# distortion-noise-and-ring-modulator-v1_1.net
KiCad netlist of a schematic drawn in EAGLE
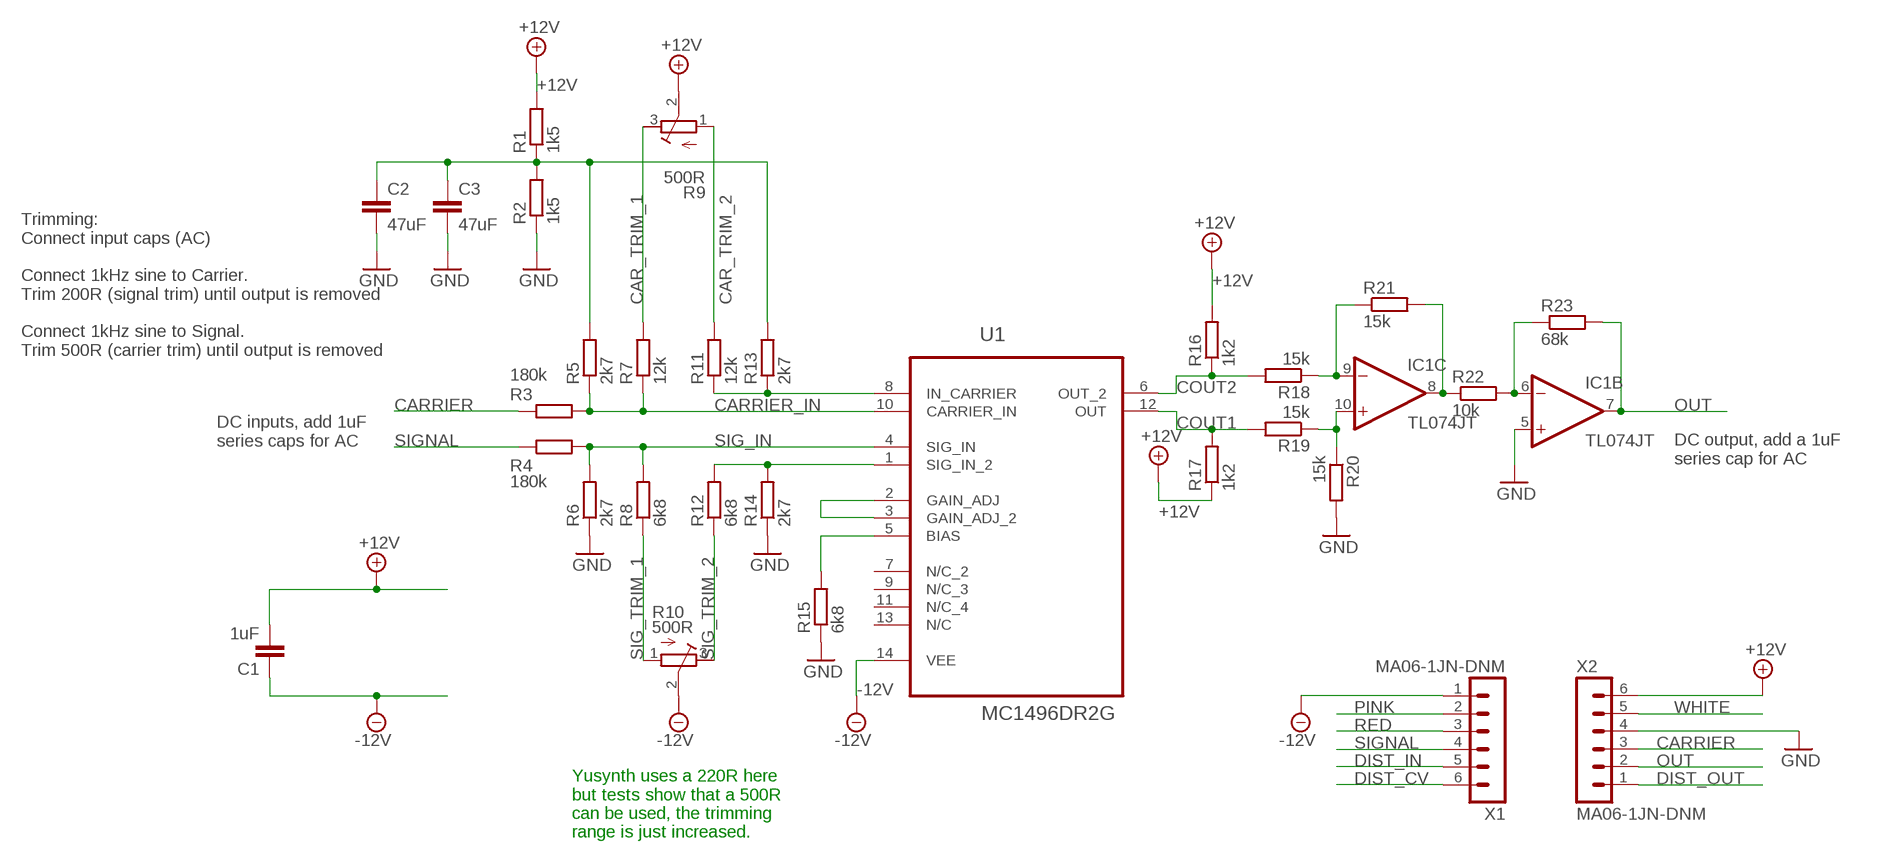
[diagram p0: schematic, sheet 1]
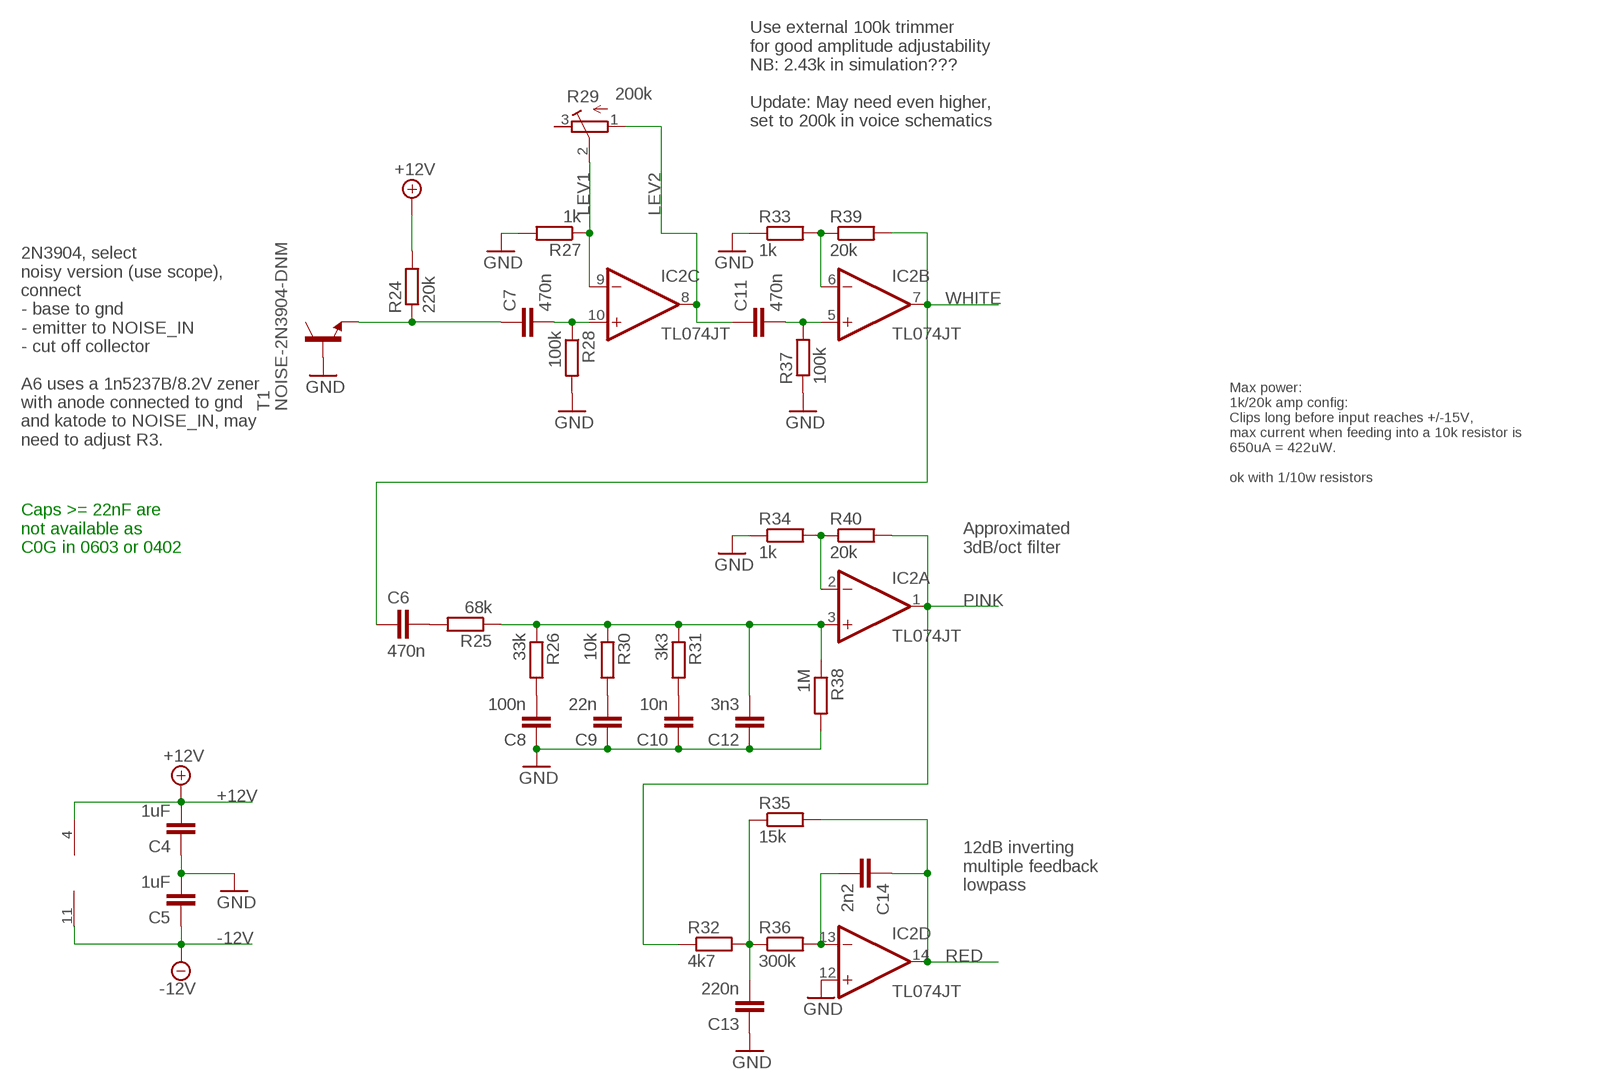
[diagram p1: schematic, sheet 2]
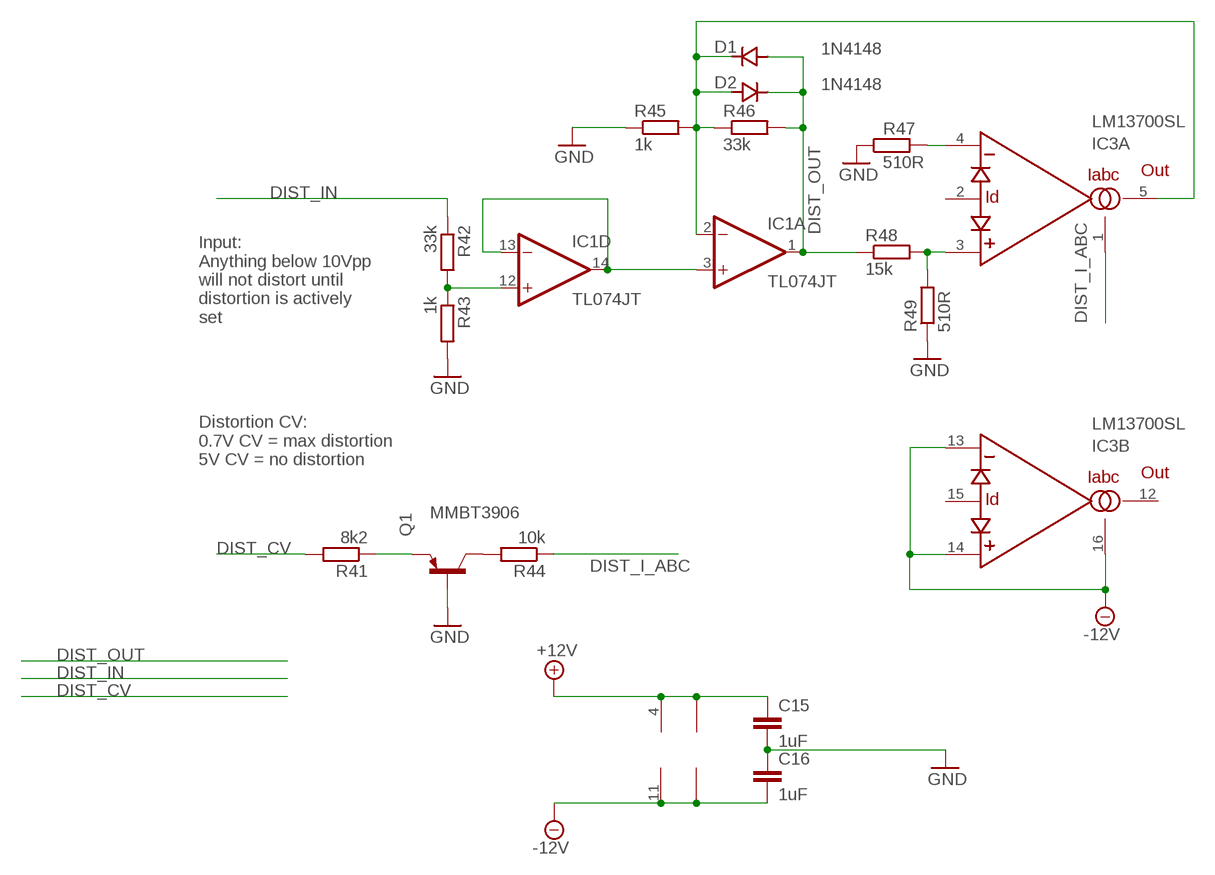
[diagram p2: schematic, sheet 3]

(export (version "E")
  (design (tool "Eeschema 10.0.6"))
  (components
    (comp (ref "C4")
      (value "1uF")
      (footprint "eagle-import:C0402-J")
      (libsource (lib "eagle-import") (part "C-EU-J0402"))
    )
    (comp (ref "C5")
      (value "1uF")
      (footprint "eagle-import:C0402-J")
      (libsource (lib "eagle-import") (part "C-EU-J0402"))
    )
    (comp (ref "C6")
      (value "470n")
      (footprint "eagle-import:C0603-J")
      (libsource (lib "eagle-import") (part "C-EU-J0603"))
    )
    (comp (ref "C7")
      (value "470n")
      (footprint "eagle-import:C0603-J")
      (libsource (lib "eagle-import") (part "C-EU-J0603"))
    )
    (comp (ref "C8")
      (value "100n")
      (footprint "eagle-import:C0402-J")
      (libsource (lib "eagle-import") (part "C-EU-J0402"))
    )
    (comp (ref "C9")
      (value "22n")
      (footprint "eagle-import:C0402-J")
      (libsource (lib "eagle-import") (part "C-EU-J0402"))
    )
    (comp (ref "C10")
      (value "10n")
      (footprint "eagle-import:C0402-J")
      (libsource (lib "eagle-import") (part "C-EU-J0402"))
    )
    (comp (ref "C11")
      (value "470n")
      (footprint "eagle-import:C0603-J")
      (libsource (lib "eagle-import") (part "C-EU-J0603"))
    )
    (comp (ref "C12")
      (value "3n3")
      (footprint "eagle-import:C0603-J")
      (libsource (lib "eagle-import") (part "C-EU-J0603"))
    )
    (comp (ref "C13")
      (value "220n")
      (footprint "eagle-import:C0402-J")
      (libsource (lib "eagle-import") (part "C-EU-J0402"))
    )
    (comp (ref "C14")
      (value "2n2")
      (footprint "eagle-import:C0603-J")
      (libsource (lib "eagle-import") (part "C-EU-J0603"))
    )
    (comp (ref "IC2")
      (value "TL074JT")
      (footprint "eagle-import:TSSOP14J")
      (libsource (lib "eagle-import") (part "TL074JT"))
    )
    (comp (ref "R24")
      (value "220k")
      (footprint "eagle-import:R0603")
      (libsource (lib "eagle-import") (part "R-EU_R0603"))
    )
    (comp (ref "R25")
      (value "68k")
      (footprint "eagle-import:R0603")
      (libsource (lib "eagle-import") (part "R-EU_R0603"))
    )
    (comp (ref "R26")
      (value "33k")
      (footprint "eagle-import:R0402")
      (libsource (lib "eagle-import") (part "R-EU_R0402"))
    )
    (comp (ref "R27")
      (value "1k")
      (footprint "eagle-import:R0402")
      (libsource (lib "eagle-import") (part "R-EU_R0402"))
    )
    (comp (ref "R28")
      (value "100k")
      (footprint "eagle-import:R0402")
      (libsource (lib "eagle-import") (part "R-EU_R0402"))
    )
    (comp (ref "R29")
      (value "200k")
      (footprint "eagle-import:RTRIM3296W")
      (libsource (lib "eagle-import") (part "R-TRIMM3296W"))
    )
    (comp (ref "R30")
      (value "10k")
      (footprint "eagle-import:R0402")
      (libsource (lib "eagle-import") (part "R-EU_R0402"))
    )
    (comp (ref "R31")
      (value "3k3")
      (footprint "eagle-import:R0402")
      (libsource (lib "eagle-import") (part "R-EU_R0402"))
    )
    (comp (ref "R32")
      (value "4k7")
      (footprint "eagle-import:R0402")
      (libsource (lib "eagle-import") (part "R-EU_R0402"))
    )
    (comp (ref "R33")
      (value "1k")
      (footprint "eagle-import:R0402")
      (libsource (lib "eagle-import") (part "R-EU_R0402"))
    )
    (comp (ref "R34")
      (value "1k")
      (footprint "eagle-import:R0402")
      (libsource (lib "eagle-import") (part "R-EU_R0402"))
    )
    (comp (ref "R35")
      (value "15k")
      (footprint "eagle-import:R0402")
      (libsource (lib "eagle-import") (part "R-EU_R0402"))
    )
    (comp (ref "R36")
      (value "300k")
      (footprint "eagle-import:R0603")
      (libsource (lib "eagle-import") (part "R-EU_R0603"))
    )
    (comp (ref "R37")
      (value "100k")
      (footprint "eagle-import:R0402")
      (libsource (lib "eagle-import") (part "R-EU_R0402"))
    )
    (comp (ref "R38")
      (value "1M")
      (footprint "eagle-import:R0402")
      (libsource (lib "eagle-import") (part "R-EU_R0402"))
    )
    (comp (ref "R39")
      (value "20k")
      (footprint "eagle-import:R0402")
      (libsource (lib "eagle-import") (part "R-EU_R0402"))
    )
    (comp (ref "R40")
      (value "20k")
      (footprint "eagle-import:R0402")
      (libsource (lib "eagle-import") (part "R-EU_R0402"))
    )
    (comp (ref "T1")
      (value "NOISE-2N3904-DNM")
      (footprint "eagle-import:NOISE-2N3904-J")
      (libsource (lib "eagle-import") (part "NOISE-2N3904"))
    )
    (comp (ref "C15")
      (value "1uF")
      (footprint "eagle-import:C0402-J")
      (libsource (lib "eagle-import") (part "C-EU-J0402"))
    )
    (comp (ref "C16")
      (value "1uF")
      (footprint "eagle-import:C0402-J")
      (libsource (lib "eagle-import") (part "C-EU-J0402"))
    )
    (comp (ref "D1")
      (value "1N4148")
      (footprint "eagle-import:SOD323J")
      (libsource (lib "eagle-import") (part "1N4148SOD323"))
    )
    (comp (ref "D2")
      (value "1N4148")
      (footprint "eagle-import:SOD323J")
      (libsource (lib "eagle-import") (part "1N4148SOD323"))
    )
    (comp (ref "IC1")
      (value "TL074JT")
      (footprint "eagle-import:TSSOP14J")
      (libsource (lib "eagle-import") (part "TL074JT"))
    )
    (comp (ref "IC3")
      (value "LM13700SL")
      (footprint "eagle-import:SO16-NARROW-J")
      (libsource (lib "eagle-import") (part "LM13700SL"))
    )
    (comp (ref "Q1")
      (value "MMBT3906")
      (footprint "eagle-import:SOT23-BEC")
      (libsource (lib "eagle-import") (part "MMBT3906SMDLT1"))
    )
    (comp (ref "R41")
      (value "8k2")
      (footprint "eagle-import:R0603")
      (libsource (lib "eagle-import") (part "R-EU_R0603"))
    )
    (comp (ref "R42")
      (value "33k")
      (footprint "eagle-import:R0402")
      (libsource (lib "eagle-import") (part "R-EU_R0402"))
    )
    (comp (ref "R43")
      (value "1k")
      (footprint "eagle-import:R0402")
      (libsource (lib "eagle-import") (part "R-EU_R0402"))
    )
    (comp (ref "R44")
      (value "10k")
      (footprint "eagle-import:R0402")
      (libsource (lib "eagle-import") (part "R-EU_R0402"))
    )
    (comp (ref "R45")
      (value "1k")
      (footprint "eagle-import:R0402")
      (libsource (lib "eagle-import") (part "R-EU_R0402"))
    )
    (comp (ref "R46")
      (value "33k")
      (footprint "eagle-import:R0402")
      (libsource (lib "eagle-import") (part "R-EU_R0402"))
    )
    (comp (ref "R47")
      (value "510R")
      (footprint "eagle-import:R0402")
      (libsource (lib "eagle-import") (part "R-EU_R0402"))
    )
    (comp (ref "R48")
      (value "15k")
      (footprint "eagle-import:R0402")
      (libsource (lib "eagle-import") (part "R-EU_R0402"))
    )
    (comp (ref "R49")
      (value "510R")
      (footprint "eagle-import:R0402")
      (libsource (lib "eagle-import") (part "R-EU_R0402"))
    )
    (comp (ref "C1")
      (value "1uF")
      (footprint "eagle-import:C0402-J")
      (libsource (lib "eagle-import") (part "C-EU-J0402"))
    )
    (comp (ref "C2")
      (value "47uF")
      (footprint "eagle-import:C1206")
      (libsource (lib "eagle-import") (part "C-EUC1206"))
    )
    (comp (ref "C3")
      (value "47uF")
      (footprint "eagle-import:C1206")
      (libsource (lib "eagle-import") (part "C-EUC1206"))
    )
    (comp (ref "R1")
      (value "1k5")
      (footprint "eagle-import:R0402")
      (libsource (lib "eagle-import") (part "R-EU_R0402"))
    )
    (comp (ref "R2")
      (value "1k5")
      (footprint "eagle-import:R0402")
      (libsource (lib "eagle-import") (part "R-EU_R0402"))
    )
    (comp (ref "R3")
      (value "180k")
      (footprint "eagle-import:R0402")
      (libsource (lib "eagle-import") (part "R-EU_R0402"))
    )
    (comp (ref "R4")
      (value "180k")
      (footprint "eagle-import:R0402")
      (libsource (lib "eagle-import") (part "R-EU_R0402"))
    )
    (comp (ref "R5")
      (value "2k7")
      (footprint "eagle-import:R0603")
      (libsource (lib "eagle-import") (part "R-EU_R0603"))
    )
    (comp (ref "R6")
      (value "2k7")
      (footprint "eagle-import:R0603")
      (libsource (lib "eagle-import") (part "R-EU_R0603"))
    )
    (comp (ref "R7")
      (value "12k")
      (footprint "eagle-import:R0402")
      (libsource (lib "eagle-import") (part "R-EU_R0402"))
    )
    (comp (ref "R8")
      (value "6k8")
      (footprint "eagle-import:R0603")
      (libsource (lib "eagle-import") (part "R-EU_R0603"))
    )
    (comp (ref "R9")
      (value "500R")
      (footprint "eagle-import:RTRIM3296X")
      (libsource (lib "eagle-import") (part "R-TRIMM3296X"))
    )
    (comp (ref "R10")
      (value "500R")
      (footprint "eagle-import:RTRIM3296X")
      (libsource (lib "eagle-import") (part "R-TRIMM3296X"))
    )
    (comp (ref "R11")
      (value "12k")
      (footprint "eagle-import:R0402")
      (libsource (lib "eagle-import") (part "R-EU_R0402"))
    )
    (comp (ref "R12")
      (value "6k8")
      (footprint "eagle-import:R0603")
      (libsource (lib "eagle-import") (part "R-EU_R0603"))
    )
    (comp (ref "R13")
      (value "2k7")
      (footprint "eagle-import:R0603")
      (libsource (lib "eagle-import") (part "R-EU_R0603"))
    )
    (comp (ref "R14")
      (value "2k7")
      (footprint "eagle-import:R0603")
      (libsource (lib "eagle-import") (part "R-EU_R0603"))
    )
    (comp (ref "R15")
      (value "6k8")
      (footprint "eagle-import:R0603")
      (libsource (lib "eagle-import") (part "R-EU_R0603"))
    )
    (comp (ref "R16")
      (value "1k2")
      (footprint "eagle-import:R0603")
      (libsource (lib "eagle-import") (part "R-EU_R0603"))
    )
    (comp (ref "R17")
      (value "1k2")
      (footprint "eagle-import:R0603")
      (libsource (lib "eagle-import") (part "R-EU_R0603"))
    )
    (comp (ref "R18")
      (value "15k")
      (footprint "eagle-import:R0402")
      (libsource (lib "eagle-import") (part "R-EU_R0402"))
    )
    (comp (ref "R19")
      (value "15k")
      (footprint "eagle-import:R0402")
      (libsource (lib "eagle-import") (part "R-EU_R0402"))
    )
    (comp (ref "R20")
      (value "15k")
      (footprint "eagle-import:R0402")
      (libsource (lib "eagle-import") (part "R-EU_R0402"))
    )
    (comp (ref "R21")
      (value "15k")
      (footprint "eagle-import:R0402")
      (libsource (lib "eagle-import") (part "R-EU_R0402"))
    )
    (comp (ref "R22")
      (value "10k")
      (footprint "eagle-import:R0402")
      (libsource (lib "eagle-import") (part "R-EU_R0402"))
    )
    (comp (ref "R23")
      (value "68k")
      (footprint "eagle-import:R0603")
      (libsource (lib "eagle-import") (part "R-EU_R0603"))
    )
    (comp (ref "U1")
      (value "MC1496DR2G")
      (footprint "eagle-import:SOIC127P600X175-14N")
      (libsource (lib "eagle-import") (part "MC1496DR2G"))
    )
    (comp (ref "X1")
      (value "MA06-1JN-DNM")
      (footprint "eagle-import:MA06N-1J")
      (libsource (lib "eagle-import") (part "MA06-1JN"))
    )
    (comp (ref "X2")
      (value "MA06-1JN-DNM")
      (footprint "eagle-import:MA06N-1J")
      (libsource (lib "eagle-import") (part "MA06-1JN"))
    )
  )
  (nets
    (net (code "1") (name "+12V") (class "Default")
      (node (ref "C1") (pin "2") (pinfunction "2_2") (pintype "passive"))
      (node (ref "C15") (pin "1") (pinfunction "1_1") (pintype "passive"))
      (node (ref "C4") (pin "2") (pinfunction "2_2") (pintype "passive"))
      (node (ref "IC1") (pin "4") (pinfunction "V+_4") (pintype "power_in"))
      (node (ref "IC2") (pin "4") (pinfunction "V+_4") (pintype "power_in"))
      (node (ref "IC3") (pin "11") (pinfunction "V+_11") (pintype "bidirectional"))
      (node (ref "R1") (pin "2") (pinfunction "2_2") (pintype "passive"))
      (node (ref "R16") (pin "2") (pinfunction "2_2") (pintype "passive"))
      (node (ref "R17") (pin "1") (pinfunction "1_1") (pintype "passive"))
      (node (ref "R24") (pin "2") (pinfunction "2_2") (pintype "passive"))
      (node (ref "R9") (pin "2") (pinfunction "S_2") (pintype "passive"))
      (node (ref "X2") (pin "6") (pinfunction "6_6") (pintype "passive"))
    )
    (net (code "2") (name "-12V") (class "Default")
      (node (ref "C1") (pin "1") (pinfunction "1_1") (pintype "passive"))
      (node (ref "C16") (pin "2") (pinfunction "2_2") (pintype "passive"))
      (node (ref "C5") (pin "1") (pinfunction "1_1") (pintype "passive"))
      (node (ref "IC1") (pin "11") (pinfunction "V-_11") (pintype "power_in"))
      (node (ref "IC2") (pin "11") (pinfunction "V-_11") (pintype "power_in"))
      (node (ref "IC3") (pin "13") (pinfunction "-IN_13") (pintype "bidirectional"))
      (node (ref "IC3") (pin "14") (pinfunction "+IN_14") (pintype "bidirectional"))
      (node (ref "IC3") (pin "16") (pinfunction "IABC_16") (pintype "bidirectional"))
      (node (ref "IC3") (pin "6") (pinfunction "V-_6") (pintype "bidirectional"))
      (node (ref "R10") (pin "2") (pinfunction "S_2") (pintype "passive"))
      (node (ref "U1") (pin "14") (pinfunction "VEE_14") (pintype "passive"))
      (node (ref "X1") (pin "1") (pinfunction "1_1") (pintype "passive"))
    )
    (net (code "3") (name "CARRIER") (class "Default")
      (node (ref "R3") (pin "1") (pinfunction "1_1") (pintype "passive"))
      (node (ref "X2") (pin "3") (pinfunction "3_3") (pintype "passive"))
    )
    (net (code "4") (name "CARRIER_IN") (class "Default")
      (node (ref "R3") (pin "2") (pinfunction "2_2") (pintype "passive"))
      (node (ref "R5") (pin "1") (pinfunction "1_1") (pintype "passive"))
      (node (ref "R7") (pin "1") (pinfunction "1_1") (pintype "passive"))
      (node (ref "U1") (pin "10") (pinfunction "CARRIER_IN_10") (pintype "power_in"))
    )
    (net (code "5") (name "CAR_TRIM_1") (class "Default")
      (node (ref "R7") (pin "2") (pinfunction "2_2") (pintype "passive"))
      (node (ref "R9") (pin "3") (pinfunction "E_3") (pintype "passive"))
    )
    (net (code "6") (name "CAR_TRIM_2") (class "Default")
      (node (ref "R11") (pin "2") (pinfunction "2_2") (pintype "passive"))
      (node (ref "R9") (pin "1") (pinfunction "A_1") (pintype "passive"))
    )
    (net (code "7") (name "COUT1") (class "Default")
      (node (ref "R17") (pin "2") (pinfunction "2_2") (pintype "passive"))
      (node (ref "R19") (pin "2") (pinfunction "2_2") (pintype "passive"))
      (node (ref "U1") (pin "12") (pinfunction "OUT_12") (pintype "output"))
    )
    (net (code "8") (name "COUT2") (class "Default")
      (node (ref "R16") (pin "1") (pinfunction "1_1") (pintype "passive"))
      (node (ref "R18") (pin "2") (pinfunction "2_2") (pintype "passive"))
      (node (ref "U1") (pin "6") (pinfunction "OUT_2_6") (pintype "output"))
    )
    (net (code "9") (name "DIST_CV") (class "Default")
      (node (ref "R41") (pin "2") (pinfunction "2_2") (pintype "passive"))
      (node (ref "X1") (pin "6") (pinfunction "6_6") (pintype "passive"))
    )
    (net (code "10") (name "DIST_IN") (class "Default")
      (node (ref "R42") (pin "1") (pinfunction "1_1") (pintype "passive"))
      (node (ref "X1") (pin "5") (pinfunction "5_5") (pintype "passive"))
    )
    (net (code "11") (name "DIST_I_ABC") (class "Default")
      (node (ref "IC3") (pin "1") (pinfunction "IABC_1") (pintype "bidirectional"))
      (node (ref "R44") (pin "1") (pinfunction "1_1") (pintype "passive"))
    )
    (net (code "12") (name "DIST_OUT") (class "Default")
      (node (ref "D1") (pin "2") (pinfunction "A_2") (pintype "passive"))
      (node (ref "D2") (pin "1") (pinfunction "C_1") (pintype "passive"))
      (node (ref "IC1") (pin "1") (pinfunction "OUT_1") (pintype "output"))
      (node (ref "R46") (pin "2") (pinfunction "2_2") (pintype "passive"))
      (node (ref "R48") (pin "1") (pinfunction "1_1") (pintype "passive"))
      (node (ref "X2") (pin "1") (pinfunction "1_1") (pintype "passive"))
    )
    (net (code "13") (name "GND") (class "Default")
      (node (ref "C10") (pin "1") (pinfunction "1_1") (pintype "passive"))
      (node (ref "C12") (pin "1") (pinfunction "1_1") (pintype "passive"))
      (node (ref "C13") (pin "1") (pinfunction "1_1") (pintype "passive"))
      (node (ref "C15") (pin "2") (pinfunction "2_2") (pintype "passive"))
      (node (ref "C16") (pin "1") (pinfunction "1_1") (pintype "passive"))
      (node (ref "C2") (pin "2") (pinfunction "2_2") (pintype "passive"))
      (node (ref "C3") (pin "2") (pinfunction "2_2") (pintype "passive"))
      (node (ref "C4") (pin "1") (pinfunction "1_1") (pintype "passive"))
      (node (ref "C5") (pin "2") (pinfunction "2_2") (pintype "passive"))
      (node (ref "C8") (pin "1") (pinfunction "1_1") (pintype "passive"))
      (node (ref "C9") (pin "1") (pinfunction "1_1") (pintype "passive"))
      (node (ref "IC1") (pin "5") (pinfunction "+IN_5") (pintype "input"))
      (node (ref "IC2") (pin "12") (pinfunction "+IN_12") (pintype "input"))
      (node (ref "Q1") (pin "B") (pinfunction "B_B") (pintype "passive"))
      (node (ref "R14") (pin "1") (pinfunction "1_1") (pintype "passive"))
      (node (ref "R15") (pin "1") (pinfunction "1_1") (pintype "passive"))
      (node (ref "R2") (pin "1") (pinfunction "1_1") (pintype "passive"))
      (node (ref "R20") (pin "2") (pinfunction "2_2") (pintype "passive"))
      (node (ref "R27") (pin "2") (pinfunction "2_2") (pintype "passive"))
      (node (ref "R28") (pin "2") (pinfunction "2_2") (pintype "passive"))
      (node (ref "R33") (pin "1") (pinfunction "1_1") (pintype "passive"))
      (node (ref "R34") (pin "1") (pinfunction "1_1") (pintype "passive"))
      (node (ref "R37") (pin "1") (pinfunction "1_1") (pintype "passive"))
      (node (ref "R38") (pin "2") (pinfunction "2_2") (pintype "passive"))
      (node (ref "R43") (pin "2") (pinfunction "2_2") (pintype "passive"))
      (node (ref "R45") (pin "1") (pinfunction "1_1") (pintype "passive"))
      (node (ref "R47") (pin "1") (pinfunction "1_1") (pintype "passive"))
      (node (ref "R49") (pin "1") (pinfunction "1_1") (pintype "passive"))
      (node (ref "R6") (pin "1") (pinfunction "1_1") (pintype "passive"))
      (node (ref "T1") (pin "B") (pinfunction "B_B") (pintype "passive"))
      (node (ref "X2") (pin "4") (pinfunction "4_4") (pintype "passive"))
    )
    (net (code "14") (name "LEV1") (class "Default")
      (node (ref "IC2") (pin "9") (pinfunction "-IN_9") (pintype "input"))
      (node (ref "R27") (pin "1") (pinfunction "1_1") (pintype "passive"))
      (node (ref "R29") (pin "2") (pinfunction "S_2") (pintype "passive"))
    )
    (net (code "15") (name "LEV2") (class "Default")
      (node (ref "C11") (pin "1") (pinfunction "1_1") (pintype "passive"))
      (node (ref "IC2") (pin "8") (pinfunction "OUT_8") (pintype "output"))
      (node (ref "R29") (pin "1") (pinfunction "A_1") (pintype "passive"))
    )
    (net (code "16") (name "Net-(C2-Pad1)") (class "Default")
      (node (ref "C2") (pin "1") (pinfunction "1_1") (pintype "passive"))
      (node (ref "C3") (pin "1") (pinfunction "1_1") (pintype "passive"))
      (node (ref "R1") (pin "1") (pinfunction "1_1") (pintype "passive"))
      (node (ref "R13") (pin "2") (pinfunction "2_2") (pintype "passive"))
      (node (ref "R2") (pin "2") (pinfunction "2_2") (pintype "passive"))
      (node (ref "R5") (pin "2") (pinfunction "2_2") (pintype "passive"))
    )
    (net (code "17") (name "Net-(C6-Pad2)") (class "Default")
      (node (ref "C6") (pin "2") (pinfunction "2_2") (pintype "passive"))
      (node (ref "R25") (pin "2") (pinfunction "2_2") (pintype "passive"))
    )
    (net (code "18") (name "Net-(C7-Pad1)") (class "Default")
      (node (ref "C7") (pin "1") (pinfunction "1_1") (pintype "passive"))
      (node (ref "R24") (pin "1") (pinfunction "1_1") (pintype "passive"))
      (node (ref "T1") (pin "E") (pinfunction "E_E") (pintype "passive"))
    )
    (net (code "19") (name "Net-(C8-Pad2)") (class "Default")
      (node (ref "C8") (pin "2") (pinfunction "2_2") (pintype "passive"))
      (node (ref "R26") (pin "2") (pinfunction "2_2") (pintype "passive"))
    )
    (net (code "20") (name "Net-(C9-Pad2)") (class "Default")
      (node (ref "C9") (pin "2") (pinfunction "2_2") (pintype "passive"))
      (node (ref "R30") (pin "2") (pinfunction "2_2") (pintype "passive"))
    )
    (net (code "21") (name "Net-(C10-Pad2)") (class "Default")
      (node (ref "C10") (pin "2") (pinfunction "2_2") (pintype "passive"))
      (node (ref "R31") (pin "2") (pinfunction "2_2") (pintype "passive"))
    )
    (net (code "22") (name "Net-(C13-Pad2)") (class "Default")
      (node (ref "C13") (pin "2") (pinfunction "2_2") (pintype "passive"))
      (node (ref "R32") (pin "2") (pinfunction "2_2") (pintype "passive"))
      (node (ref "R35") (pin "1") (pinfunction "1_1") (pintype "passive"))
      (node (ref "R36") (pin "1") (pinfunction "1_1") (pintype "passive"))
    )
    (net (code "23") (name "Net-(D1-C)") (class "Default")
      (node (ref "D1") (pin "1") (pinfunction "C_1") (pintype "passive"))
      (node (ref "D2") (pin "2") (pinfunction "A_2") (pintype "passive"))
      (node (ref "IC1") (pin "2") (pinfunction "-IN_2") (pintype "input"))
      (node (ref "IC3") (pin "5") (pinfunction "OUT_5") (pintype "bidirectional"))
      (node (ref "R45") (pin "2") (pinfunction "2_2") (pintype "passive"))
      (node (ref "R46") (pin "1") (pinfunction "1_1") (pintype "passive"))
    )
    (net (code "24") (name "Net-(IC1A-+IN)") (class "Default")
      (node (ref "IC1") (pin "13") (pinfunction "-IN_13") (pintype "input"))
      (node (ref "IC1") (pin "14") (pinfunction "OUT_14") (pintype "output"))
      (node (ref "IC1") (pin "3") (pinfunction "+IN_3") (pintype "input"))
    )
    (net (code "25") (name "Net-(IC1B--IN)") (class "Default")
      (node (ref "IC1") (pin "6") (pinfunction "-IN_6") (pintype "input"))
      (node (ref "R22") (pin "2") (pinfunction "2_2") (pintype "passive"))
      (node (ref "R23") (pin "1") (pinfunction "1_1") (pintype "passive"))
    )
    (net (code "26") (name "Net-(IC1C-+IN)") (class "Default")
      (node (ref "IC1") (pin "10") (pinfunction "+IN_10") (pintype "input"))
      (node (ref "R19") (pin "1") (pinfunction "1_1") (pintype "passive"))
      (node (ref "R20") (pin "1") (pinfunction "1_1") (pintype "passive"))
    )
    (net (code "27") (name "Net-(IC1C--IN)") (class "Default")
      (node (ref "IC1") (pin "9") (pinfunction "-IN_9") (pintype "input"))
      (node (ref "R18") (pin "1") (pinfunction "1_1") (pintype "passive"))
      (node (ref "R21") (pin "1") (pinfunction "1_1") (pintype "passive"))
    )
    (net (code "28") (name "Net-(IC1C-OUT)") (class "Default")
      (node (ref "IC1") (pin "8") (pinfunction "OUT_8") (pintype "output"))
      (node (ref "R21") (pin "2") (pinfunction "2_2") (pintype "passive"))
      (node (ref "R22") (pin "1") (pinfunction "1_1") (pintype "passive"))
    )
    (net (code "29") (name "Net-(IC1D-+IN)") (class "Default")
      (node (ref "IC1") (pin "12") (pinfunction "+IN_12") (pintype "input"))
      (node (ref "R42") (pin "2") (pinfunction "2_2") (pintype "passive"))
      (node (ref "R43") (pin "1") (pinfunction "1_1") (pintype "passive"))
    )
    (net (code "30") (name "Net-(IC2A-+IN)") (class "Default")
      (node (ref "C12") (pin "2") (pinfunction "2_2") (pintype "passive"))
      (node (ref "IC2") (pin "3") (pinfunction "+IN_3") (pintype "input"))
      (node (ref "R25") (pin "1") (pinfunction "1_1") (pintype "passive"))
      (node (ref "R26") (pin "1") (pinfunction "1_1") (pintype "passive"))
      (node (ref "R30") (pin "1") (pinfunction "1_1") (pintype "passive"))
      (node (ref "R31") (pin "1") (pinfunction "1_1") (pintype "passive"))
      (node (ref "R38") (pin "1") (pinfunction "1_1") (pintype "passive"))
    )
    (net (code "31") (name "Net-(IC2A--IN)") (class "Default")
      (node (ref "IC2") (pin "2") (pinfunction "-IN_2") (pintype "input"))
      (node (ref "R34") (pin "2") (pinfunction "2_2") (pintype "passive"))
      (node (ref "R40") (pin "1") (pinfunction "1_1") (pintype "passive"))
    )
    (net (code "32") (name "Net-(IC2B-+IN)") (class "Default")
      (node (ref "C11") (pin "2") (pinfunction "2_2") (pintype "passive"))
      (node (ref "IC2") (pin "5") (pinfunction "+IN_5") (pintype "input"))
      (node (ref "R37") (pin "2") (pinfunction "2_2") (pintype "passive"))
    )
    (net (code "33") (name "Net-(IC2B--IN)") (class "Default")
      (node (ref "IC2") (pin "6") (pinfunction "-IN_6") (pintype "input"))
      (node (ref "R33") (pin "2") (pinfunction "2_2") (pintype "passive"))
      (node (ref "R39") (pin "1") (pinfunction "1_1") (pintype "passive"))
    )
    (net (code "34") (name "Net-(IC2C-+IN)") (class "Default")
      (node (ref "C7") (pin "2") (pinfunction "2_2") (pintype "passive"))
      (node (ref "IC2") (pin "10") (pinfunction "+IN_10") (pintype "input"))
      (node (ref "R28") (pin "1") (pinfunction "1_1") (pintype "passive"))
    )
    (net (code "35") (name "Net-(IC2D--IN)") (class "Default")
      (node (ref "C14") (pin "2") (pinfunction "2_2") (pintype "passive"))
      (node (ref "IC2") (pin "13") (pinfunction "-IN_13") (pintype "input"))
      (node (ref "R36") (pin "2") (pinfunction "2_2") (pintype "passive"))
    )
    (net (code "36") (name "Net-(IC3A-+IN)") (class "Default")
      (node (ref "IC3") (pin "3") (pinfunction "+IN_3") (pintype "bidirectional"))
      (node (ref "R48") (pin "2") (pinfunction "2_2") (pintype "passive"))
      (node (ref "R49") (pin "2") (pinfunction "2_2") (pintype "passive"))
    )
    (net (code "37") (name "Net-(IC3A--IN)") (class "Default")
      (node (ref "IC3") (pin "4") (pinfunction "-IN_4") (pintype "bidirectional"))
      (node (ref "R47") (pin "2") (pinfunction "2_2") (pintype "passive"))
    )
    (net (code "38") (name "Net-(Q1-PadC)") (class "Default")
      (node (ref "Q1") (pin "C") (pinfunction "C_C") (pintype "passive"))
      (node (ref "R44") (pin "2") (pinfunction "2_2") (pintype "passive"))
    )
    (net (code "39") (name "Net-(Q1-PadE)") (class "Default")
      (node (ref "Q1") (pin "E") (pinfunction "E_E") (pintype "passive"))
      (node (ref "R41") (pin "1") (pinfunction "1_1") (pintype "passive"))
    )
    (net (code "40") (name "Net-(U1-BIAS)") (class "Default")
      (node (ref "R15") (pin "2") (pinfunction "2_2") (pintype "passive"))
      (node (ref "U1") (pin "5") (pinfunction "BIAS_5") (pintype "input"))
    )
    (net (code "41") (name "Net-(U1-GAIN_ADJ)") (class "Default")
      (node (ref "U1") (pin "2") (pinfunction "GAIN_ADJ_2") (pintype "input"))
      (node (ref "U1") (pin "3") (pinfunction "GAIN_ADJ_2_3") (pintype "input"))
    )
    (net (code "42") (name "Net-(U1-IN_CARRIER)") (class "Default")
      (node (ref "R11") (pin "1") (pinfunction "1_1") (pintype "passive"))
      (node (ref "R13") (pin "1") (pinfunction "1_1") (pintype "passive"))
      (node (ref "U1") (pin "8") (pinfunction "IN_CARRIER_8") (pintype "power_in"))
    )
    (net (code "43") (name "Net-(U1-SIG_IN_2)") (class "Default")
      (node (ref "R12") (pin "2") (pinfunction "2_2") (pintype "passive"))
      (node (ref "R14") (pin "2") (pinfunction "2_2") (pintype "passive"))
      (node (ref "U1") (pin "1") (pinfunction "SIG_IN_2_1") (pintype "input"))
    )
    (net (code "44") (name "OUT") (class "Default")
      (node (ref "IC1") (pin "7") (pinfunction "OUT_7") (pintype "output"))
      (node (ref "R23") (pin "2") (pinfunction "2_2") (pintype "passive"))
      (node (ref "X2") (pin "2") (pinfunction "2_2") (pintype "passive"))
    )
    (net (code "45") (name "PINK") (class "Default")
      (node (ref "IC2") (pin "1") (pinfunction "OUT_1") (pintype "output"))
      (node (ref "R32") (pin "1") (pinfunction "1_1") (pintype "passive"))
      (node (ref "R40") (pin "2") (pinfunction "2_2") (pintype "passive"))
      (node (ref "X1") (pin "2") (pinfunction "2_2") (pintype "passive"))
    )
    (net (code "46") (name "RED") (class "Default")
      (node (ref "C14") (pin "1") (pinfunction "1_1") (pintype "passive"))
      (node (ref "IC2") (pin "14") (pinfunction "OUT_14") (pintype "output"))
      (node (ref "R35") (pin "2") (pinfunction "2_2") (pintype "passive"))
      (node (ref "X1") (pin "3") (pinfunction "3_3") (pintype "passive"))
    )
    (net (code "47") (name "SIGNAL") (class "Default")
      (node (ref "R4") (pin "1") (pinfunction "1_1") (pintype "passive"))
      (node (ref "X1") (pin "4") (pinfunction "4_4") (pintype "passive"))
    )
    (net (code "48") (name "SIG_IN") (class "Default")
      (node (ref "R4") (pin "2") (pinfunction "2_2") (pintype "passive"))
      (node (ref "R6") (pin "2") (pinfunction "2_2") (pintype "passive"))
      (node (ref "R8") (pin "2") (pinfunction "2_2") (pintype "passive"))
      (node (ref "U1") (pin "4") (pinfunction "SIG_IN_4") (pintype "input"))
    )
    (net (code "49") (name "SIG_TRIM_1") (class "Default")
      (node (ref "R10") (pin "1") (pinfunction "A_1") (pintype "passive"))
      (node (ref "R8") (pin "1") (pinfunction "1_1") (pintype "passive"))
    )
    (net (code "50") (name "SIG_TRIM_2") (class "Default")
      (node (ref "R10") (pin "3") (pinfunction "E_3") (pintype "passive"))
      (node (ref "R12") (pin "1") (pinfunction "1_1") (pintype "passive"))
    )
    (net (code "51") (name "WHITE") (class "Default")
      (node (ref "C6") (pin "1") (pinfunction "1_1") (pintype "passive"))
      (node (ref "IC2") (pin "7") (pinfunction "OUT_7") (pintype "output"))
      (node (ref "R39") (pin "2") (pinfunction "2_2") (pintype "passive"))
      (node (ref "X2") (pin "5") (pinfunction "5_5") (pintype "passive"))
    )
    (net (code "52") (name "unconnected-(IC3A-ID-Pad2)") (class "Default")
      (node (ref "IC3") (pin "2") (pinfunction "ID_2") (pintype "bidirectional"))
    )
    (net (code "53") (name "unconnected-(IC3B-ID-Pad15)") (class "Default")
      (node (ref "IC3") (pin "15") (pinfunction "ID_15") (pintype "bidirectional"))
    )
    (net (code "54") (name "unconnected-(IC3B-OUT-Pad12)") (class "Default")
      (node (ref "IC3") (pin "12") (pinfunction "OUT_12") (pintype "bidirectional"))
    )
    (net (code "55") (name "unconnected-(R29-E-Pad3)") (class "Default")
      (node (ref "R29") (pin "3") (pinfunction "E_3") (pintype "passive"))
    )
    (net (code "56") (name "unconnected-(U1-N{slash}C-Pad13)") (class "Default")
      (node (ref "U1") (pin "13") (pinfunction "N/C_13") (pintype "no_connect"))
    )
    (net (code "57") (name "unconnected-(U1-N{slash}C_2-Pad7)") (class "Default")
      (node (ref "U1") (pin "7") (pinfunction "N/C_2_7") (pintype "no_connect"))
    )
    (net (code "58") (name "unconnected-(U1-N{slash}C_3-Pad9)") (class "Default")
      (node (ref "U1") (pin "9") (pinfunction "N/C_3_9") (pintype "no_connect"))
    )
    (net (code "59") (name "unconnected-(U1-N{slash}C_4-Pad11)") (class "Default")
      (node (ref "U1") (pin "11") (pinfunction "N/C_4_11") (pintype "no_connect"))
    )
  )
)
